# LED.net
KiCad netlist of a schematic drawn in Altium Designer
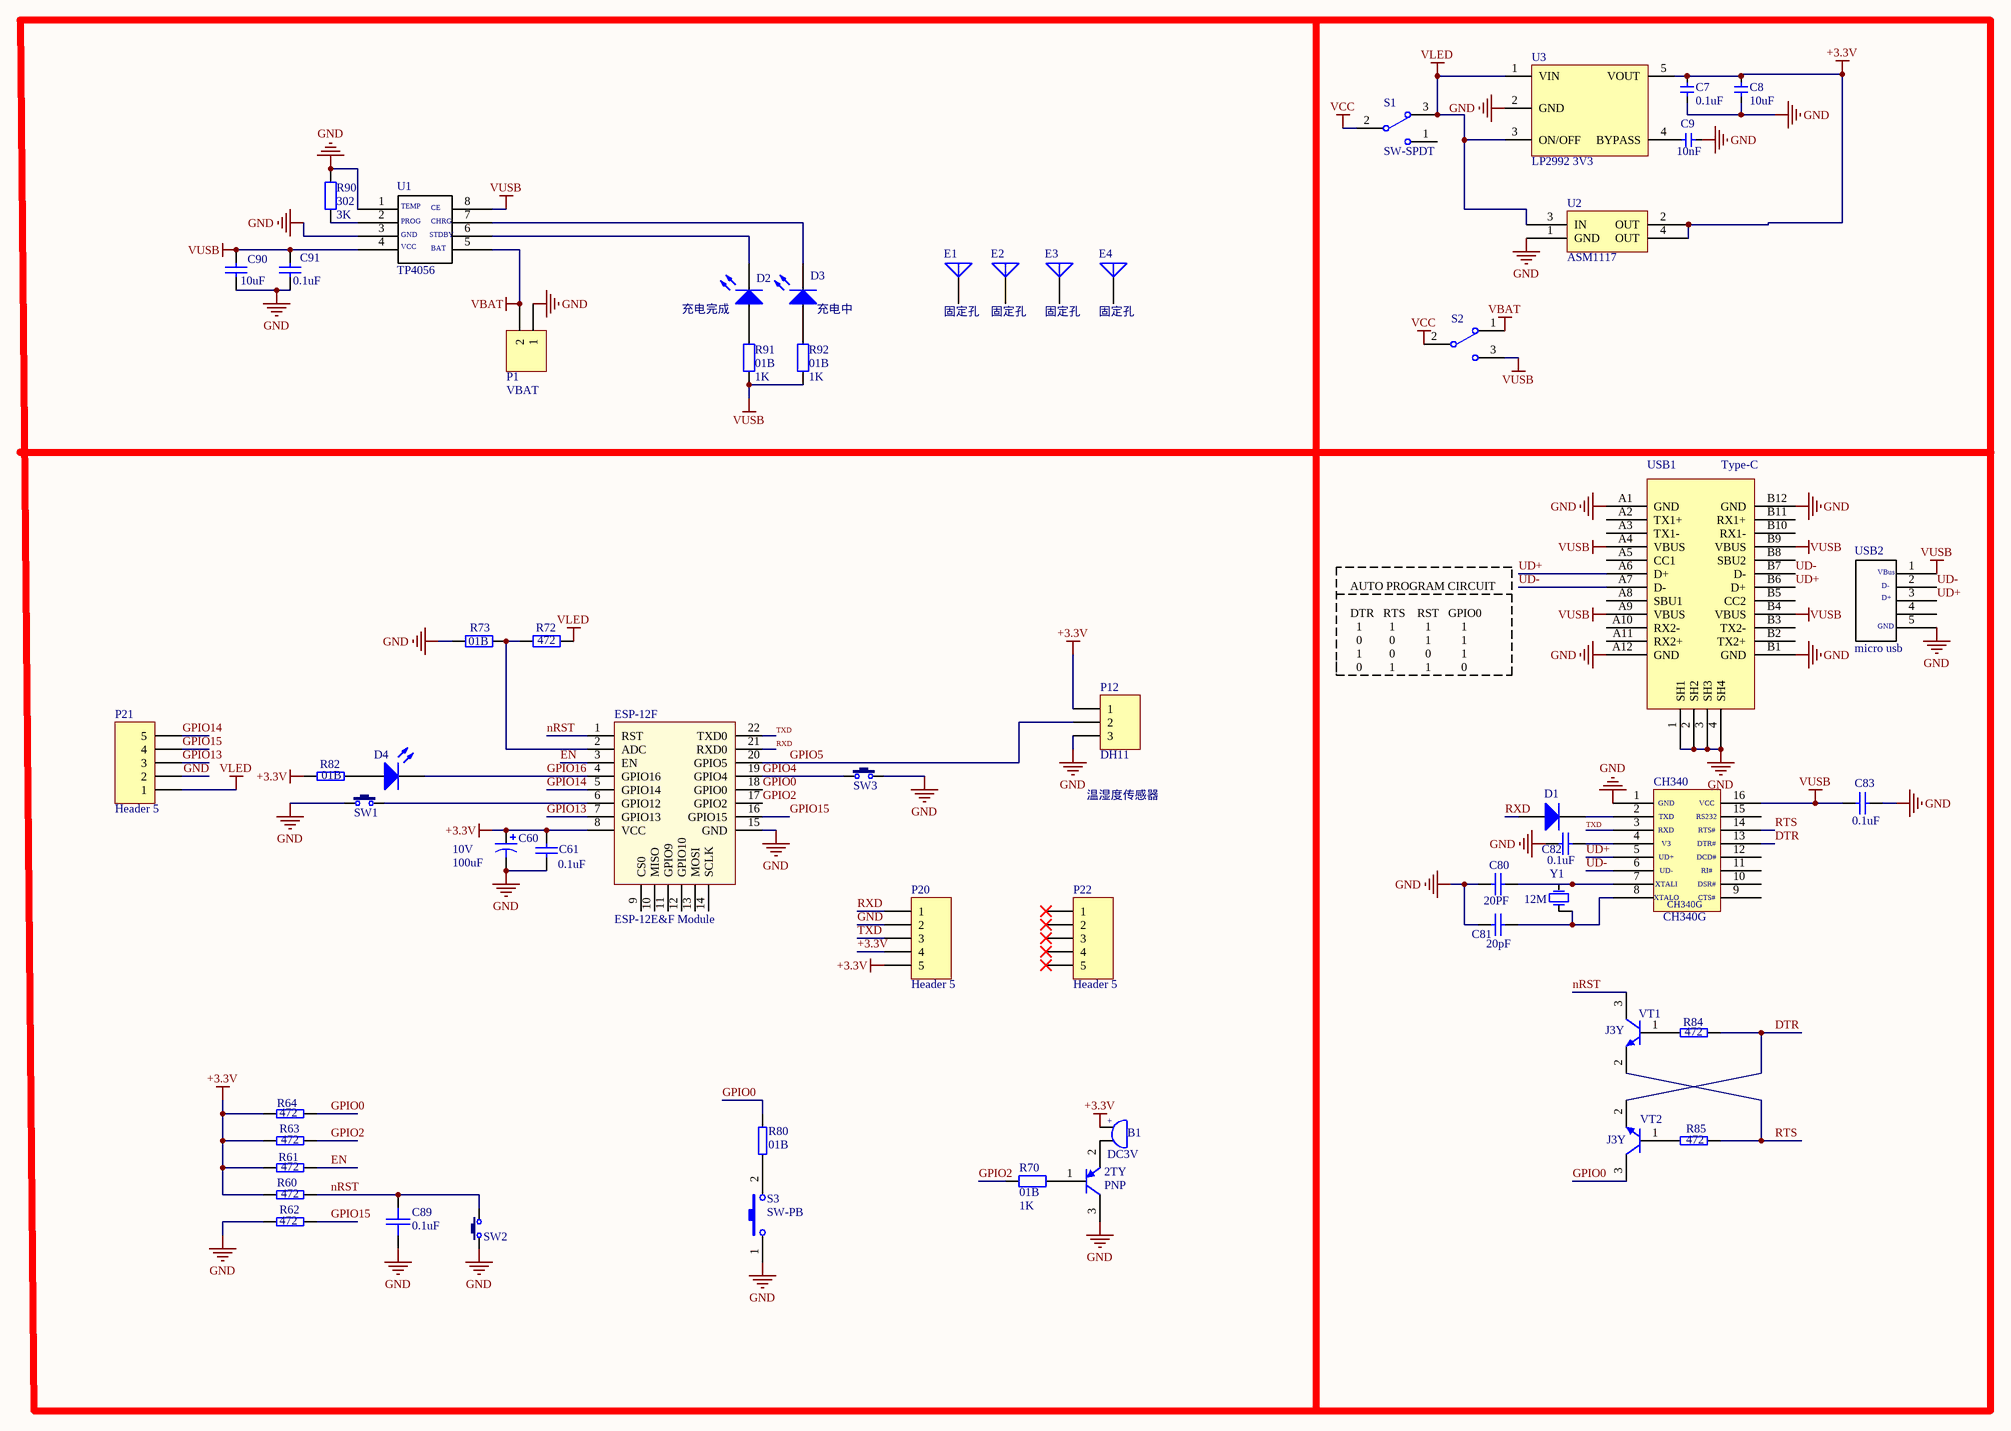
[diagram p0: LED点阵时钟.SchDoc]

(export (version "E")
  (design (tool "Eeschema 10.0.6"))
  (components
    (comp (ref "2TY")
      (value "PNP")
      (footprint "2TY")
      (description "PNP Bipolar Transistor")
      (fields (field (name "PUBLISHER") "Altium Limited"))
      (libsource (lib "Miscellaneous Devices") (part "PNP"))
    )
    (comp (ref "B1")
      (value "DC3V")
      (footprint "BEEP 7.6x12x7.5 - X")
      (description "蜂鸣器")
      (fields (field (name "版权归属") "源创客"))
      (libsource (lib "未分类器件") (part "BEEP"))
    )
    (comp (ref "C7")
      (value "0.1uF")
      (footprint "0603-1")
      (description "Capacitor")
      (libsource (lib "MyPcbLib") (part "电容-0402"))
    )
    (comp (ref "C8")
      (value "10uF")
      (footprint "0603-1")
      (description "Capacitor")
      (libsource (lib "MyPcbLib") (part "电容-0603"))
    )
    (comp (ref "C9")
      (value "10nF")
      (footprint "0603-1")
      (description "Capacitor")
      (libsource (lib "MyPcbLib") (part "电容-0402"))
    )
    (comp (ref "C60")
      (value "10V")
      (footprint "CM C(5*5.4)")
      (description "Polarized Capacitor (Surface Mount)")
      (fields (field (name "ALTIUM_VALUE") "100uF") (field (name "PUBLISHER") "Altium Limited"))
      (libsource (lib "Miscellaneous Devices") (part "Cap Pol3"))
    )
    (comp (ref "C61")
      (value "0.1uF")
      (footprint "0603-1")
      (description "Capacitor")
      (fields (field (name "PUBLISHER") "Altium Limited"))
      (libsource (lib "Miscellaneous Devices") (part "Cap"))
    )
    (comp (ref "C80")
      (value "20PF")
      (footprint "0603-1")
      (fields (field (name "ALTIUM_VALUE") "20pF") (field (name "PUBLISHER") "Altium Limited"))
      (libsource (lib "Miscellaneous Devices") (part "Cap"))
    )
    (comp (ref "C81")
      (value "~")
      (footprint "0603-1")
      (fields (field (name "PUBLISHER") "Altium Limited"))
      (libsource (lib "Miscellaneous Devices") (part "Cap"))
    )
    (comp (ref "C82")
      (value "0.1uF")
      (footprint "0603-1")
      (description "Capacitor")
      (fields (field (name "PUBLISHER") "Altium Limited"))
      (libsource (lib "Miscellaneous Devices") (part "Cap"))
    )
    (comp (ref "C83")
      (value "0.1uF")
      (footprint "0603-1")
      (description "Capacitor")
      (fields (field (name "PUBLISHER") "Altium Limited"))
      (libsource (lib "Miscellaneous Devices") (part "Cap"))
    )
    (comp (ref "C89")
      (value "0.1uF")
      (footprint "0603-1")
      (description "Surface mount capacitor 0402")
      (libsource (lib "Vowstar_Basic_Device") (part "SMT_C_0402"))
    )
    (comp (ref "C90")
      (value "10uF")
      (footprint "0603-1")
      (description "Capacitor")
      (fields (field (name "PUBLISHER") "Altium Limited"))
      (libsource (lib "Miscellaneous Devices") (part "Cap"))
    )
    (comp (ref "C91")
      (value "0.1uF")
      (footprint "0603-1")
      (description "Capacitor")
      (fields (field (name "PUBLISHER") "Altium Limited"))
      (libsource (lib "Miscellaneous Devices") (part "Cap"))
    )
    (comp (ref "CH340") (value "CH340G") (footprint "SOP16_M") (libsource (lib "Schlib2") (part "CH340G")))
    (comp (ref "D1")
      (value "~")
      (footprint "T4 -Mini")
      (description "1 Amp General Purpose Rectifier")
      (fields (field (name "PUBLISHER") "Altium Limited"))
      (libsource (lib "Miscellaneous Devices") (part "Diode 1N4003"))
    )
    (comp (ref "D2")
      (value "~")
      (footprint "LED 0603G")
      (description "Typical INFRARED GaAs LED")
      (fields (field (name "PUBLISHER") "Altium Limited"))
      (libsource (lib "Miscellaneous Devices") (part "LED0"))
    )
    (comp (ref "D3")
      (value "~")
      (footprint "LED 0603R")
      (description "Typical INFRARED GaAs LED")
      (fields (field (name "PUBLISHER") "Altium Limited"))
      (libsource (lib "Miscellaneous Devices") (part "LED0"))
    )
    (comp (ref "D4")
      (value "~")
      (footprint "LED 0603G")
      (description "Typical INFRARED GaAs LED")
      (fields (field (name "PUBLISHER") "Altium Limited"))
      (libsource (lib "Miscellaneous Devices") (part "LED0"))
    )
    (comp (ref "E1")
      (value "固定孔")
      (footprint "M2.2")
      (description "Generic Antenna")
      (fields (field (name "PUBLISHER") "Altium Limited"))
      (libsource (lib "Miscellaneous Devices") (part "Antenna"))
    )
    (comp (ref "E2")
      (value "固定孔")
      (footprint "M2.2")
      (description "Generic Antenna")
      (fields (field (name "PUBLISHER") "Altium Limited"))
      (libsource (lib "Miscellaneous Devices") (part "Antenna"))
    )
    (comp (ref "E3")
      (value "固定孔")
      (footprint "M2.2")
      (description "Generic Antenna")
      (fields (field (name "PUBLISHER") "Altium Limited"))
      (libsource (lib "Miscellaneous Devices") (part "Antenna"))
    )
    (comp (ref "E4")
      (value "固定孔")
      (footprint "M2.2")
      (description "Generic Antenna")
      (fields (field (name "PUBLISHER") "Altium Limited"))
      (libsource (lib "Miscellaneous Devices") (part "Antenna"))
    )
    (comp (ref "ESP-12F")
      (value "ESP-12E&F Module")
      (footprint "ESP-12E&F Module")
      (libsource (lib "ESP-12E&F Module") (part "ESP-12E&F Module"))
    )
    (comp (ref "P1")
      (value "VBAT")
      (footprint "XH2.54-2P_H")
      (description "Header, 2-Pin")
      (fields (field (name "PUBLISHER") "Altium Limited"))
      (libsource (lib "Miscellaneous Connectors") (part "Header 2"))
    )
    (comp (ref "P12")
      (value "DH11")
      (footprint "HDR1X3")
      (description "Header, 3-Pin")
      (fields (field (name "PUBLISHER") "Altium Limited"))
      (libsource (lib "Miscellaneous Connectors") (part "Header 3"))
    )
    (comp (ref "P20")
      (value "Header 5")
      (footprint "HDR1X5")
      (description "Header, 5-Pin")
      (fields (field (name "PUBLISHER") "Altium Limited"))
      (libsource (lib "Miscellaneous Connectors") (part "Header 5"))
    )
    (comp (ref "P21")
      (value "Header 5")
      (footprint "HDR1X5")
      (description "Header, 5-Pin")
      (fields (field (name "PUBLISHER") "Altium Limited"))
      (libsource (lib "") (part "Header 5_1"))
    )
    (comp (ref "P22")
      (value "Header 5")
      (footprint "HDR1X5")
      (description "Header, 5-Pin")
      (fields (field (name "PUBLISHER") "Altium Limited"))
      (libsource (lib "Miscellaneous Connectors") (part "Header 5"))
    )
    (comp (ref "R60")
      (value "472")
      (footprint "0603-1")
      (description "Surface mount resistor 0402")
      (libsource (lib "Vowstar_Basic_Device") (part "SMT_R_0402"))
    )
    (comp (ref "R61")
      (value "472")
      (footprint "0603-1")
      (description "Surface mount resistor 0402")
      (libsource (lib "Vowstar_Basic_Device") (part "SMT_R_0402"))
    )
    (comp (ref "R62")
      (value "472")
      (footprint "0603-1")
      (description "Surface mount resistor 0402")
      (libsource (lib "Vowstar_Basic_Device") (part "SMT_R_0402"))
    )
    (comp (ref "R63")
      (value "472")
      (footprint "0603-1")
      (description "Surface mount resistor 0402")
      (libsource (lib "Vowstar_Basic_Device") (part "SMT_R_0402"))
    )
    (comp (ref "R64")
      (value "472")
      (footprint "0603-1")
      (description "Surface mount resistor 0402")
      (libsource (lib "Vowstar_Basic_Device") (part "SMT_R_0402"))
    )
    (comp (ref "R70")
      (value "01B")
      (footprint "0603-1")
      (description "Resistor")
      (fields (field (name "ALTIUM_VALUE") "1K") (field (name "PUBLISHER") "Altium Limited"))
      (libsource (lib "Miscellaneous Devices") (part "Res2"))
    )
    (comp (ref "R72")
      (value "472")
      (footprint "0603-1")
      (description "Resistor")
      (fields (field (name "PUBLISHER") "Altium Limited"))
      (libsource (lib "") (part "Res2_2"))
    )
    (comp (ref "R73")
      (value "01B")
      (footprint "0603-1")
      (description "Resistor")
      (fields (field (name "PUBLISHER") "Altium Limited"))
      (libsource (lib "") (part "Res2_2"))
    )
    (comp (ref "R80")
      (value "01B")
      (footprint "0603-1")
      (description "Surface mount resistor 0402")
      (libsource (lib "Vowstar_Basic_Device") (part "SMT_R_0402"))
    )
    (comp (ref "R82")
      (value "01B")
      (footprint "0603-1")
      (description "Surface mount resistor 0402")
      (libsource (lib "Vowstar_Basic_Device") (part "SMT_R_0402"))
    )
    (comp (ref "R84")
      (value "472")
      (footprint "0603-1")
      (description "Surface mount resistor 0402")
      (libsource (lib "Vowstar_Basic_Device") (part "SMT_R_0402"))
    )
    (comp (ref "R85")
      (value "472")
      (footprint "0603-1")
      (description "Surface mount resistor 0402")
      (libsource (lib "Vowstar_Basic_Device") (part "SMT_R_0402"))
    )
    (comp (ref "R90")
      (value "302")
      (footprint "0603-1")
      (description "Resistor")
      (fields (field (name "ALTIUM_VALUE") "3K") (field (name "PUBLISHER") "Altium Limited"))
      (libsource (lib "") (part "Res2_1"))
    )
    (comp (ref "R91")
      (value "01B")
      (footprint "0603-1")
      (description "Resistor")
      (fields (field (name "ALTIUM_VALUE") "1K") (field (name "PUBLISHER") "Altium Limited"))
      (libsource (lib "") (part "Res2_3"))
    )
    (comp (ref "R92")
      (value "01B")
      (footprint "0603-1")
      (description "Resistor")
      (fields (field (name "ALTIUM_VALUE") "1K") (field (name "PUBLISHER") "Altium Limited"))
      (libsource (lib "") (part "Res2_1"))
    )
    (comp (ref "S1")
      (value "SW-SPDT")
      (footprint "SS-12F23")
      (description "SPDT Subminiature Toggle Switch, Right Angle Mounting, Vertical Actuation")
      (fields (field (name "PUBLISHER") "Altium Limited"))
      (libsource (lib "Miscellaneous Devices") (part "SW-SPDT"))
    )
    (comp (ref "S2")
      (value "~")
      (footprint "MSK-12C01-07 - 7pin")
      (description "1路波动开关")
      (fields (field (name "版权归属") "源创客"))
      (libsource (lib "按键-开关") (part "SSW-1P"))
    )
    (comp (ref "S3")
      (value "SW-PB")
      (footprint "SW2 _1")
      (description "微动开关")
      (fields (field (name "PUBLISHER") "Altium Limited"))
      (libsource (lib "Schlib2") (part "SW-PB"))
    )
    (comp (ref "SW1")
      (value "6x6x5")
      (footprint "TSW DIP-6*6*7_V")
      (description "侧按直插6x6轻触开关")
      (fields (field (name "版权归属") "源创客"))
      (libsource (lib "") (part "TSW DIP-6x6_V_1"))
    )
    (comp (ref "SW2")
      (value "6x6x5")
      (footprint "TSW DIP-6*6*7_V")
      (description "侧按直插6x6轻触开关")
      (fields (field (name "版权归属") "源创客"))
      (libsource (lib "按键-开关") (part "TSW DIP-6x6_V"))
    )
    (comp (ref "SW3")
      (value "6x6x5")
      (footprint "TSW DIP-6*6*7_V")
      (description "侧按直插6x6轻触开关")
      (fields (field (name "版权归属") "源创客"))
      (libsource (lib "") (part "TSW DIP-6x6_V_1"))
    )
    (comp (ref "U1") (value "TP4056") (footprint "SOP8_N") (libsource (lib "Schlib1") (part "TP4056")))
    (comp (ref "U2")
      (value "ASM1117")
      (footprint "SOT-223")
      (description "3.3V稳压芯片")
      (libsource (lib "Schlib2") (part "ASM1117"))
    )
    (comp (ref "U3")
      (value "LP2992 3V3")
      (footprint "SOT23-5")
      (description "LDO")
      (libsource (lib "MyPcbLib") (part "LP2992"))
    )
    (comp (ref "USB1")
      (value "Type-C")
      (footprint "USB_TYPE_C_FEMALE_12_16P")
      (libsource (lib "MyPcbLib") (part "USB-Type-C-TOP"))
    )
    (comp (ref "USB2")
      (value "micro usb")
      (footprint "USB-micro_C")
      (libsource (lib "Schlib1") (part "micro usb"))
    )
    (comp (ref "VT1")
      (value "J3Y")
      (footprint "J3Y")
      (description "Surface mount NPN transistor, package SOT-23")
      (libsource (lib "Vowstar_Basic_Device") (part "SMT_TRIODE_NPN"))
    )
    (comp (ref "VT2")
      (value "J3Y")
      (footprint "J3Y")
      (description "Surface mount NPN transistor, package SOT-23")
      (libsource (lib "Vowstar_Basic_Device") (part "SMT_TRIODE_NPN"))
    )
    (comp (ref "Y1")
      (value "12M")
      (footprint "XTAL-49S DIP")
      (description "晶振")
      (fields (field (name "Comment") "XTAL") (field (name "PUBLISHER") "Altium Limited"))
      (libsource (lib "Schlib2") (part "XTAL"))
    )
  )
  (nets
    (net (code "1") (name "+3.3V") (class "Default")
      (node (ref "B1") (pin "1") (pinfunction "1_1") (pintype "passive"))
      (node (ref "C60") (pin "1") (pinfunction "1_1") (pintype "passive"))
      (node (ref "C61") (pin "2") (pinfunction "2_2") (pintype "passive"))
      (node (ref "C7") (pin "2") (pinfunction "2_2") (pintype "passive"))
      (node (ref "C8") (pin "2") (pinfunction "2_2") (pintype "passive"))
      (node (ref "ESP-12F") (pin "8") (pinfunction "VCC_8") (pintype "passive"))
      (node (ref "P12") (pin "1") (pinfunction "1_1") (pintype "passive"))
      (node (ref "P20") (pin "4") (pinfunction "4_4") (pintype "passive"))
      (node (ref "P20") (pin "5") (pinfunction "5_5") (pintype "passive"))
      (node (ref "R60") (pin "1") (pinfunction "1_1") (pintype "passive"))
      (node (ref "R61") (pin "1") (pinfunction "1_1") (pintype "passive"))
      (node (ref "R63") (pin "1") (pinfunction "1_1") (pintype "passive"))
      (node (ref "R64") (pin "1") (pinfunction "1_1") (pintype "passive"))
      (node (ref "R82") (pin "2") (pinfunction "2_2") (pintype "passive"))
      (node (ref "U2") (pin "2") (pinfunction "OUT_2") (pintype "passive"))
      (node (ref "U2") (pin "4") (pinfunction "OUT_4") (pintype "passive"))
      (node (ref "U3") (pin "5") (pinfunction "VOUT_5") (pintype "passive"))
    )
    (net (code "2") (name "/DTR") (class "Default")
      (node (ref "CH340") (pin "13") (pintype "passive"))
      (node (ref "R84") (pin "2") (pinfunction "2_2") (pintype "passive"))
      (node (ref "VT2") (pin "2") (pinfunction "E_2") (pintype "passive"))
    )
    (net (code "3") (name "/EN") (class "Default")
      (node (ref "ESP-12F") (pin "3") (pinfunction "EN_3") (pintype "passive"))
      (node (ref "R61") (pin "2") (pinfunction "2_2") (pintype "passive"))
    )
    (net (code "4") (name "/GPIO0") (class "Default")
      (node (ref "ESP-12F") (pin "18") (pinfunction "GPIO0_18") (pintype "passive"))
      (node (ref "R64") (pin "2") (pinfunction "2_2") (pintype "passive"))
      (node (ref "R80") (pin "2") (pinfunction "2_2") (pintype "passive"))
      (node (ref "VT2") (pin "3") (pinfunction "C_3") (pintype "passive"))
    )
    (net (code "5") (name "/GPIO2") (class "Default")
      (node (ref "ESP-12F") (pin "17") (pinfunction "GPIO2_17") (pintype "passive"))
      (node (ref "R63") (pin "2") (pinfunction "2_2") (pintype "passive"))
      (node (ref "R70") (pin "2") (pinfunction "2_2") (pintype "passive"))
    )
    (net (code "6") (name "/GPIO4") (class "Default")
      (node (ref "ESP-12F") (pin "19") (pinfunction "GPIO4_19") (pintype "passive"))
      (node (ref "SW3") (pin "1") (pinfunction "1_1") (pintype "passive"))
    )
    (net (code "7") (name "/GPIO5") (class "Default")
      (node (ref "ESP-12F") (pin "20") (pinfunction "GPIO5_20") (pintype "passive"))
      (node (ref "P12") (pin "2") (pinfunction "2_2") (pintype "passive"))
    )
    (net (code "8") (name "/GPIO13") (class "Default")
      (node (ref "ESP-12F") (pin "7") (pinfunction "GPIO13_7") (pintype "passive"))
      (node (ref "P21") (pin "3") (pinfunction "3_3") (pintype "passive"))
    )
    (net (code "9") (name "/GPIO14") (class "Default")
      (node (ref "ESP-12F") (pin "5") (pinfunction "GPIO14_5") (pintype "passive"))
      (node (ref "P21") (pin "5") (pinfunction "5_5") (pintype "passive"))
    )
    (net (code "10") (name "/GPIO15") (class "Default")
      (node (ref "ESP-12F") (pin "16") (pinfunction "GPIO15_16") (pintype "passive"))
      (node (ref "P21") (pin "4") (pinfunction "4_4") (pintype "passive"))
      (node (ref "R62") (pin "2") (pinfunction "2_2") (pintype "passive"))
    )
    (net (code "11") (name "/GPIO16") (class "Default")
      (node (ref "D4") (pin "2") (pinfunction "K_2") (pintype "passive"))
      (node (ref "ESP-12F") (pin "4") (pinfunction "GPIO16_4") (pintype "passive"))
    )
    (net (code "12") (name "/RTS") (class "Default")
      (node (ref "CH340") (pin "14") (pintype "passive"))
      (node (ref "R85") (pin "2") (pinfunction "2_2") (pintype "passive"))
      (node (ref "VT1") (pin "2") (pinfunction "E_2") (pintype "passive"))
    )
    (net (code "13") (name "/RXD") (class "Default")
      (node (ref "D1") (pin "1") (pinfunction "A_1") (pintype "passive"))
      (node (ref "ESP-12F") (pin "21") (pinfunction "RXD0_21") (pintype "passive"))
      (node (ref "P20") (pin "1") (pinfunction "1_1") (pintype "passive"))
    )
    (net (code "14") (name "/TXD") (class "Default")
      (node (ref "CH340") (pin "3") (pintype "passive"))
      (node (ref "ESP-12F") (pin "22") (pinfunction "TXD0_22") (pintype "passive"))
      (node (ref "P20") (pin "3") (pinfunction "3_3") (pintype "passive"))
    )
    (net (code "15") (name "/UD+") (class "Default")
      (node (ref "CH340") (pin "5") (pintype "passive"))
      (node (ref "USB1") (pin "A6") (pinfunction "D+_A6") (pintype "passive"))
      (node (ref "USB1") (pin "B6") (pinfunction "D+_B6") (pintype "passive"))
      (node (ref "USB2") (pin "3") (pinfunction "3_3") (pintype "passive"))
    )
    (net (code "16") (name "/UD-") (class "Default")
      (node (ref "CH340") (pin "6") (pintype "passive"))
      (node (ref "USB1") (pin "A7") (pinfunction "D-_A7") (pintype "passive"))
      (node (ref "USB1") (pin "B7") (pinfunction "D-_B7") (pintype "passive"))
      (node (ref "USB2") (pin "2") (pinfunction "2_2") (pintype "passive"))
    )
    (net (code "17") (name "/nRST") (class "Default")
      (node (ref "C89") (pin "1") (pinfunction "1_1") (pintype "passive"))
      (node (ref "ESP-12F") (pin "1") (pinfunction "RST_1") (pintype "passive"))
      (node (ref "R60") (pin "2") (pinfunction "2_2") (pintype "passive"))
      (node (ref "SW2") (pin "2") (pinfunction "2_2") (pintype "passive"))
      (node (ref "VT1") (pin "3") (pinfunction "C_3") (pintype "passive"))
    )
    (net (code "18") (name "GND") (class "Default")
      (node (ref "2TY") (pin "3") (pinfunction "C_3") (pintype "passive"))
      (node (ref "C60") (pin "2") (pinfunction "2_2") (pintype "passive"))
      (node (ref "C61") (pin "1") (pinfunction "1_1") (pintype "passive"))
      (node (ref "C7") (pin "1") (pinfunction "1_1") (pintype "passive"))
      (node (ref "C8") (pin "1") (pinfunction "1_1") (pintype "passive"))
      (node (ref "C80") (pin "1") (pinfunction "1_1") (pintype "passive"))
      (node (ref "C81") (pin "1") (pinfunction "1_1") (pintype "passive"))
      (node (ref "C82") (pin "1") (pinfunction "1_1") (pintype "passive"))
      (node (ref "C83") (pin "2") (pinfunction "2_2") (pintype "passive"))
      (node (ref "C89") (pin "2") (pinfunction "2_2") (pintype "passive"))
      (node (ref "C9") (pin "1") (pinfunction "1_1") (pintype "passive"))
      (node (ref "C90") (pin "1") (pinfunction "1_1") (pintype "passive"))
      (node (ref "C91") (pin "1") (pinfunction "1_1") (pintype "passive"))
      (node (ref "CH340") (pin "1") (pintype "passive"))
      (node (ref "ESP-12F") (pin "15") (pinfunction "GND_15") (pintype "passive"))
      (node (ref "P1") (pin "1") (pinfunction "1_1") (pintype "passive"))
      (node (ref "P12") (pin "3") (pinfunction "3_3") (pintype "passive"))
      (node (ref "P20") (pin "2") (pinfunction "2_2") (pintype "passive"))
      (node (ref "P21") (pin "2") (pinfunction "2_2") (pintype "passive"))
      (node (ref "R62") (pin "1") (pinfunction "1_1") (pintype "passive"))
      (node (ref "R73") (pin "1") (pinfunction "1_1") (pintype "passive"))
      (node (ref "R90") (pin "1") (pinfunction "1_1") (pintype "passive"))
      (node (ref "S3") (pin "1") (pinfunction "1_1") (pintype "passive"))
      (node (ref "SW1") (pin "1") (pinfunction "1_1") (pintype "passive"))
      (node (ref "SW2") (pin "1") (pinfunction "1_1") (pintype "passive"))
      (node (ref "SW3") (pin "2") (pinfunction "2_2") (pintype "passive"))
      (node (ref "U1") (pin "1") (pinfunction "1_1") (pintype "passive"))
      (node (ref "U1") (pin "3") (pinfunction "3_3") (pintype "passive"))
      (node (ref "U2") (pin "1") (pinfunction "GND_1") (pintype "passive"))
      (node (ref "U3") (pin "2") (pinfunction "GND_2") (pintype "passive"))
      (node (ref "USB1") (pin "1") (pinfunction "SH1_1") (pintype "passive"))
      (node (ref "USB1") (pin "2") (pinfunction "SH2_2") (pintype "passive"))
      (node (ref "USB1") (pin "3") (pinfunction "SH3_3") (pintype "passive"))
      (node (ref "USB1") (pin "4") (pinfunction "SH4_4") (pintype "passive"))
      (node (ref "USB1") (pin "A1") (pinfunction "GND_A1") (pintype "passive"))
      (node (ref "USB1") (pin "A12") (pinfunction "GND_A12") (pintype "passive"))
      (node (ref "USB1") (pin "B1") (pinfunction "GND_B1") (pintype "passive"))
      (node (ref "USB1") (pin "B12") (pinfunction "GND_B12") (pintype "passive"))
      (node (ref "USB2") (pin "5") (pinfunction "5_5") (pintype "passive"))
    )
    (net (code "19") (name "Net-(2TY-B)") (class "Default")
      (node (ref "2TY") (pin "1") (pinfunction "B_1") (pintype "passive"))
      (node (ref "R70") (pin "1") (pinfunction "1_1") (pintype "passive"))
    )
    (net (code "20") (name "Net-(2TY-E)") (class "Default")
      (node (ref "2TY") (pin "2") (pinfunction "E_2") (pintype "passive"))
      (node (ref "B1") (pin "2") (pinfunction "2_2") (pintype "passive"))
    )
    (net (code "21") (name "Net-(C82-Pad2)") (class "Default")
      (node (ref "C82") (pin "2") (pinfunction "2_2") (pintype "passive"))
      (node (ref "CH340") (pin "4") (pintype "passive"))
    )
    (net (code "22") (name "Net-(D1-K)") (class "Default")
      (node (ref "CH340") (pin "2") (pintype "passive"))
      (node (ref "D1") (pin "2") (pinfunction "K_2") (pintype "passive"))
    )
    (net (code "23") (name "Net-(D2-A)") (class "Default")
      (node (ref "D2") (pin "1") (pinfunction "A_1") (pintype "passive"))
      (node (ref "R91") (pin "2") (pinfunction "2_2") (pintype "passive"))
    )
    (net (code "24") (name "Net-(D2-K)") (class "Default")
      (node (ref "D2") (pin "2") (pinfunction "K_2") (pintype "passive"))
      (node (ref "U1") (pin "6") (pinfunction "6_6") (pintype "passive"))
    )
    (net (code "25") (name "Net-(D3-A)") (class "Default")
      (node (ref "D3") (pin "1") (pinfunction "A_1") (pintype "passive"))
      (node (ref "R92") (pin "1") (pinfunction "1_1") (pintype "passive"))
    )
    (net (code "26") (name "Net-(D3-K)") (class "Default")
      (node (ref "D3") (pin "2") (pinfunction "K_2") (pintype "passive"))
      (node (ref "U1") (pin "7") (pinfunction "7_7") (pintype "passive"))
    )
    (net (code "27") (name "Net-(D4-A)") (class "Default")
      (node (ref "D4") (pin "1") (pinfunction "A_1") (pintype "passive"))
      (node (ref "R82") (pin "1") (pinfunction "1_1") (pintype "passive"))
    )
    (net (code "28") (name "Net-(ESP-12F-ADC)") (class "Default")
      (node (ref "ESP-12F") (pin "2") (pinfunction "ADC_2") (pintype "passive"))
      (node (ref "R72") (pin "1") (pinfunction "1_1") (pintype "passive"))
      (node (ref "R73") (pin "2") (pinfunction "2_2") (pintype "passive"))
    )
    (net (code "29") (name "Net-(ESP-12F-GPIO12)") (class "Default")
      (node (ref "ESP-12F") (pin "6") (pinfunction "GPIO12_6") (pintype "passive"))
      (node (ref "SW1") (pin "2") (pinfunction "2_2") (pintype "passive"))
    )
    (net (code "30") (name "Net-(R80-Pad1)") (class "Default")
      (node (ref "R80") (pin "1") (pinfunction "1_1") (pintype "passive"))
      (node (ref "S3") (pin "2") (pinfunction "2_2") (pintype "passive"))
    )
    (net (code "31") (name "Net-(R90-Pad2)") (class "Default")
      (node (ref "R90") (pin "2") (pinfunction "2_2") (pintype "passive"))
      (node (ref "U1") (pin "2") (pinfunction "2_2") (pintype "passive"))
    )
    (net (code "32") (name "Net-(U3-BYPASS)") (class "Default")
      (node (ref "C9") (pin "2") (pinfunction "2_2") (pintype "passive"))
      (node (ref "U3") (pin "4") (pinfunction "BYPASS_4") (pintype "passive"))
    )
    (net (code "33") (name "Net-(VT1-B)") (class "Default")
      (node (ref "R84") (pin "1") (pinfunction "1_1") (pintype "passive"))
      (node (ref "VT1") (pin "1") (pinfunction "B_1") (pintype "passive"))
    )
    (net (code "34") (name "Net-(VT2-B)") (class "Default")
      (node (ref "R85") (pin "1") (pinfunction "1_1") (pintype "passive"))
      (node (ref "VT2") (pin "1") (pinfunction "B_1") (pintype "passive"))
    )
    (net (code "35") (name "Net-(Y1-OSC1)") (class "Default")
      (node (ref "C81") (pin "2") (pinfunction "2_2") (pintype "passive"))
      (node (ref "CH340") (pin "8") (pintype "passive"))
      (node (ref "Y1") (pin "1") (pinfunction "OSC1_1") (pintype "passive"))
    )
    (net (code "36") (name "Net-(Y1-OSC2)") (class "Default")
      (node (ref "C80") (pin "2") (pinfunction "2_2") (pintype "passive"))
      (node (ref "CH340") (pin "7") (pintype "passive"))
      (node (ref "Y1") (pin "2") (pinfunction "OSC2_2") (pintype "passive"))
    )
    (net (code "37") (name "VBAT") (class "Default")
      (node (ref "P1") (pin "2") (pinfunction "2_2") (pintype "passive"))
      (node (ref "S2") (pin "1") (pinfunction "1_1") (pintype "passive"))
      (node (ref "U1") (pin "5") (pinfunction "5_5") (pintype "passive"))
    )
    (net (code "38") (name "VCC") (class "Default")
      (node (ref "S1") (pin "2") (pinfunction "2_2") (pintype "passive"))
      (node (ref "S2") (pin "2") (pinfunction "2_2") (pintype "passive"))
    )
    (net (code "39") (name "VLED") (class "Default")
      (node (ref "P21") (pin "1") (pinfunction "1_1") (pintype "passive"))
      (node (ref "R72") (pin "2") (pinfunction "2_2") (pintype "passive"))
      (node (ref "S1") (pin "3") (pinfunction "3_3") (pintype "passive"))
      (node (ref "U2") (pin "3") (pinfunction "IN_3") (pintype "passive"))
      (node (ref "U3") (pin "1") (pinfunction "VIN_1") (pintype "passive"))
      (node (ref "U3") (pin "3") (pinfunction "ON/OFF_3") (pintype "passive"))
    )
    (net (code "40") (name "VUSB") (class "Default")
      (node (ref "C83") (pin "1") (pinfunction "1_1") (pintype "passive"))
      (node (ref "C90") (pin "2") (pinfunction "2_2") (pintype "passive"))
      (node (ref "C91") (pin "2") (pinfunction "2_2") (pintype "passive"))
      (node (ref "CH340") (pin "16") (pintype "passive"))
      (node (ref "R91") (pin "1") (pinfunction "1_1") (pintype "passive"))
      (node (ref "R92") (pin "2") (pinfunction "2_2") (pintype "passive"))
      (node (ref "S2") (pin "3") (pinfunction "3_3") (pintype "passive"))
      (node (ref "U1") (pin "4") (pinfunction "4_4") (pintype "passive"))
      (node (ref "U1") (pin "8") (pinfunction "8_8") (pintype "passive"))
      (node (ref "USB1") (pin "A4") (pinfunction "VBUS_A4") (pintype "passive"))
      (node (ref "USB1") (pin "A9") (pinfunction "VBUS_A9") (pintype "passive"))
      (node (ref "USB1") (pin "B4") (pinfunction "VBUS_B4") (pintype "passive"))
      (node (ref "USB1") (pin "B9") (pinfunction "VBUS_B9") (pintype "passive"))
      (node (ref "USB2") (pin "1") (pinfunction "1_1") (pintype "passive"))
    )
    (net (code "41") (name "unconnected-(CH340-Pad9)") (class "Default")
      (node (ref "CH340") (pin "9") (pintype "passive"))
    )
    (net (code "42") (name "unconnected-(CH340-Pad10)") (class "Default")
      (node (ref "CH340") (pin "10") (pintype "passive"))
    )
    (net (code "43") (name "unconnected-(CH340-Pad11)") (class "Default")
      (node (ref "CH340") (pin "11") (pintype "passive"))
    )
    (net (code "44") (name "unconnected-(CH340-Pad12)") (class "Default")
      (node (ref "CH340") (pin "12") (pintype "passive"))
    )
    (net (code "45") (name "unconnected-(CH340-Pad15)") (class "Default")
      (node (ref "CH340") (pin "15") (pintype "passive"))
    )
    (net (code "46") (name "unconnected-(E1-A-Pad1)") (class "Default")
      (node (ref "E1") (pin "1") (pinfunction "A_1") (pintype "passive"))
    )
    (net (code "47") (name "unconnected-(E2-A-Pad1)") (class "Default")
      (node (ref "E2") (pin "1") (pinfunction "A_1") (pintype "passive"))
    )
    (net (code "48") (name "unconnected-(E3-A-Pad1)") (class "Default")
      (node (ref "E3") (pin "1") (pinfunction "A_1") (pintype "passive"))
    )
    (net (code "49") (name "unconnected-(E4-A-Pad1)") (class "Default")
      (node (ref "E4") (pin "1") (pinfunction "A_1") (pintype "passive"))
    )
    (net (code "50") (name "unconnected-(ESP-12F-CS0-Pad9)") (class "Default")
      (node (ref "ESP-12F") (pin "9") (pinfunction "CS0_9") (pintype "passive"))
    )
    (net (code "51") (name "unconnected-(ESP-12F-GPIO9-Pad11)") (class "Default")
      (node (ref "ESP-12F") (pin "11") (pinfunction "GPIO9_11") (pintype "passive"))
    )
    (net (code "52") (name "unconnected-(ESP-12F-GPIO10-Pad12)") (class "Default")
      (node (ref "ESP-12F") (pin "12") (pinfunction "GPIO10_12") (pintype "passive"))
    )
    (net (code "53") (name "unconnected-(ESP-12F-MISO-Pad10)") (class "Default")
      (node (ref "ESP-12F") (pin "10") (pinfunction "MISO_10") (pintype "passive"))
    )
    (net (code "54") (name "unconnected-(ESP-12F-MOSI-Pad13)") (class "Default")
      (node (ref "ESP-12F") (pin "13") (pinfunction "MOSI_13") (pintype "passive"))
    )
    (net (code "55") (name "unconnected-(ESP-12F-SCLK-Pad14)") (class "Default")
      (node (ref "ESP-12F") (pin "14") (pinfunction "SCLK_14") (pintype "passive"))
    )
    (net (code "56") (name "unconnected-(P22-Pad1)") (class "Default")
      (node (ref "P22") (pin "1") (pinfunction "1_1") (pintype "passive+no_connect"))
    )
    (net (code "57") (name "unconnected-(P22-Pad2)") (class "Default")
      (node (ref "P22") (pin "2") (pinfunction "2_2") (pintype "passive+no_connect"))
    )
    (net (code "58") (name "unconnected-(P22-Pad3)") (class "Default")
      (node (ref "P22") (pin "3") (pinfunction "3_3") (pintype "passive+no_connect"))
    )
    (net (code "59") (name "unconnected-(P22-Pad4)") (class "Default")
      (node (ref "P22") (pin "4") (pinfunction "4_4") (pintype "passive+no_connect"))
    )
    (net (code "60") (name "unconnected-(P22-Pad5)") (class "Default")
      (node (ref "P22") (pin "5") (pinfunction "5_5") (pintype "passive+no_connect"))
    )
    (net (code "61") (name "unconnected-(S1-Pad1)") (class "Default")
      (node (ref "S1") (pin "1") (pinfunction "1_1") (pintype "passive"))
    )
    (net (code "62") (name "unconnected-(USB1-CC1-PadA5)") (class "Default")
      (node (ref "USB1") (pin "A5") (pinfunction "CC1_A5") (pintype "passive"))
    )
    (net (code "63") (name "unconnected-(USB1-CC2-PadB5)") (class "Default")
      (node (ref "USB1") (pin "B5") (pinfunction "CC2_B5") (pintype "passive"))
    )
    (net (code "64") (name "unconnected-(USB1-RX1+-PadB11)") (class "Default")
      (node (ref "USB1") (pin "B11") (pinfunction "RX1+_B11") (pintype "passive"))
    )
    (net (code "65") (name "unconnected-(USB1-RX1--PadB10)") (class "Default")
      (node (ref "USB1") (pin "B10") (pinfunction "RX1-_B10") (pintype "passive"))
    )
    (net (code "66") (name "unconnected-(USB1-RX2+-PadA11)") (class "Default")
      (node (ref "USB1") (pin "A11") (pinfunction "RX2+_A11") (pintype "passive"))
    )
    (net (code "67") (name "unconnected-(USB1-RX2--PadA10)") (class "Default")
      (node (ref "USB1") (pin "A10") (pinfunction "RX2-_A10") (pintype "passive"))
    )
    (net (code "68") (name "unconnected-(USB1-SBU1-PadA8)") (class "Default")
      (node (ref "USB1") (pin "A8") (pinfunction "SBU1_A8") (pintype "passive"))
    )
    (net (code "69") (name "unconnected-(USB1-SBU2-PadB8)") (class "Default")
      (node (ref "USB1") (pin "B8") (pinfunction "SBU2_B8") (pintype "passive"))
    )
    (net (code "70") (name "unconnected-(USB1-TX1+-PadA2)") (class "Default")
      (node (ref "USB1") (pin "A2") (pinfunction "TX1+_A2") (pintype "passive"))
    )
    (net (code "71") (name "unconnected-(USB1-TX1--PadA3)") (class "Default")
      (node (ref "USB1") (pin "A3") (pinfunction "TX1-_A3") (pintype "passive"))
    )
    (net (code "72") (name "unconnected-(USB1-TX2+-PadB2)") (class "Default")
      (node (ref "USB1") (pin "B2") (pinfunction "TX2+_B2") (pintype "passive"))
    )
    (net (code "73") (name "unconnected-(USB1-TX2--PadB3)") (class "Default")
      (node (ref "USB1") (pin "B3") (pinfunction "TX2-_B3") (pintype "passive"))
    )
    (net (code "74") (name "unconnected-(USB2-Pad4)") (class "Default")
      (node (ref "USB2") (pin "4") (pinfunction "4_4") (pintype "passive"))
    )
  )
)
